# Schematic_v1_0.net
KiCad netlist of a schematic drawn in EAGLE
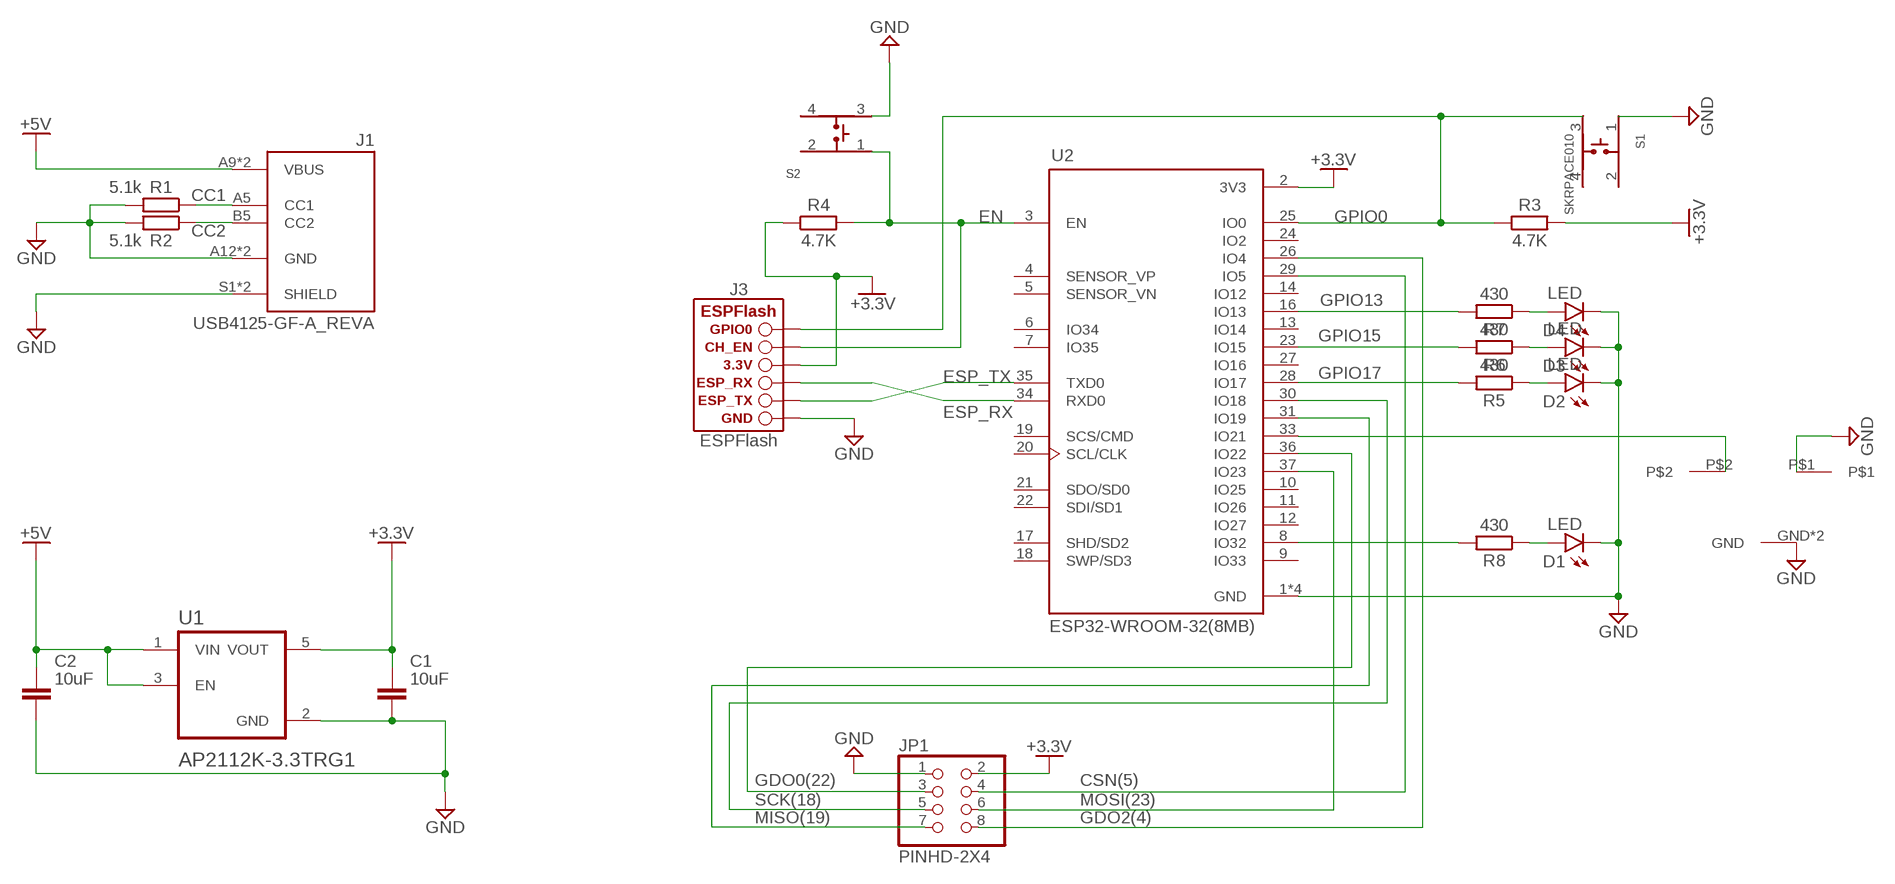
[diagram p0: schematic, sheet 1]

(export (version "E")
  (design (tool "Eeschema 10.0.6"))
  (components
    (comp (ref "C1")
      (value "10uF")
      (footprint "eagle-import:CAPC1608X85")
      (libsource (lib "eagle-import") (part "CCHIP-0603(1608-METRIC)_"))
    )
    (comp (ref "C2")
      (value "10uF")
      (footprint "eagle-import:CAPC1608X85")
      (libsource (lib "eagle-import") (part "CCHIP-0603(1608-METRIC)_"))
    )
    (comp (ref "D1")
      (value "LED")
      (footprint "eagle-import:LEDC1608X80N_FLAT-R")
      (libsource (lib "eagle-import") (part "CHIP-FLAT-R_0603-0.80MM"))
    )
    (comp (ref "D2")
      (value "LED")
      (footprint "eagle-import:LEDC1608X80N_FLAT-R")
      (libsource (lib "eagle-import") (part "CHIP-FLAT-R_0603-0.80MM"))
    )
    (comp (ref "D3")
      (value "LED")
      (footprint "eagle-import:LEDC1608X80N_FLAT-R")
      (libsource (lib "eagle-import") (part "CHIP-FLAT-R_0603-0.80MM"))
    )
    (comp (ref "D4")
      (value "LED")
      (footprint "eagle-import:LEDC1608X80N_FLAT-R")
      (libsource (lib "eagle-import") (part "CHIP-FLAT-R_0603-0.80MM"))
    )
    (comp (ref "J1")
      (value "USB4125-GF-A_REVA")
      (footprint "eagle-import:CUI_UJC-VP-3-SMT-TR")
      (fields (field (name "MANUFACTURER") "CUI Devices"))
      (libsource (lib "eagle-import") (part "UJC-VP-3-SMT-TR"))
    )
    (comp (ref "J3")
      (value "ESPFLASH-2X3-2.54-PLAIN")
      (footprint "eagle-import:2X3-2.54-PLAIN")
      (libsource (lib "eagle-import") (part "ESPFLASH-2X3-2.54-PLAIN"))
    )
    (comp (ref "JP1")
      (value "PINHD-2X4")
      (footprint "eagle-import:2X04")
      (libsource (lib "eagle-import") (part "PINHD-2X4"))
    )
    (comp (ref "R1")
      (value "5.1k")
      (footprint "eagle-import:RESC1608X60")
      (libsource (lib "eagle-import") (part "RCHIP-0603(1608-METRIC)_"))
    )
    (comp (ref "R2")
      (value "5.1k")
      (footprint "eagle-import:RESC1608X60")
      (libsource (lib "eagle-import") (part "RCHIP-0603(1608-METRIC)_"))
    )
    (comp (ref "R3")
      (value "4.7K")
      (footprint "eagle-import:RESC1608X60")
      (libsource (lib "eagle-import") (part "RCHIP-0603(1608-METRIC)_"))
    )
    (comp (ref "R4")
      (value "4.7K")
      (footprint "eagle-import:RESC1608X60")
      (libsource (lib "eagle-import") (part "RCHIP-0603(1608-METRIC)_"))
    )
    (comp (ref "R5")
      (value "430")
      (footprint "eagle-import:RESC1608X60")
      (libsource (lib "eagle-import") (part "RCHIP-0603(1608-METRIC)_"))
    )
    (comp (ref "R6")
      (value "430")
      (footprint "eagle-import:RESC1608X60")
      (libsource (lib "eagle-import") (part "RCHIP-0603(1608-METRIC)_"))
    )
    (comp (ref "R7")
      (value "430")
      (footprint "eagle-import:RESC1608X60")
      (libsource (lib "eagle-import") (part "RCHIP-0603(1608-METRIC)_"))
    )
    (comp (ref "R8")
      (value "430")
      (footprint "eagle-import:RESC1608X60")
      (libsource (lib "eagle-import") (part "RCHIP-0603(1608-METRIC)_"))
    )
    (comp (ref "S1")
      (value "SKRPACE010")
      (footprint "eagle-import:SW_SKRPACE010")
      (fields (field (name "MANUFACTURER") "ALPS"))
      (libsource (lib "eagle-import") (part "SKRPACE010"))
    )
    (comp (ref "S2")
      (value "SKRPACE010")
      (footprint "eagle-import:SW_SKRPACE010")
      (fields (field (name "MANUFACTURER") "ALPS"))
      (libsource (lib "eagle-import") (part "SKRPACE010"))
    )
    (comp (ref "U$1")
      (value "MOMENTARY-SWITCH")
      (footprint "eagle-import:SWITCH-MOMENTARY")
      (libsource (lib "eagle-import") (part "MOMENTARY-SWITCH"))
    )
    (comp (ref "U1")
      (value "AP2112K-3.3TRG1")
      (footprint "eagle-import:SOT95P285X140-5N")
      (fields (field (name "MANUFACTURER") "Diodes Inc."))
      (libsource (lib "eagle-import") (part "AP2112K-3.3TRG1"))
    )
    (comp (ref "U2")
      (value "ESP32-WROOM-32(8MB)")
      (footprint "eagle-import:MODULE_ESP32-WROOM-32(8MB)")
      (fields (field (name "MANUFACTURER") "Espressif Systems"))
      (libsource (lib "eagle-import") (part "ESP32-WROOM-32(8MB)"))
    )
  )
  (nets
    (net (code "1") (name "+3.3V") (class "Default")
      (node (ref "C1") (pin "1") (pinfunction "1_1") (pintype "passive"))
      (node (ref "J3") (pin "2") (pinfunction "3.3V_2") (pintype "passive"))
      (node (ref "JP1") (pin "2") (pinfunction "2_2") (pintype "passive"))
      (node (ref "R3") (pin "2") (pinfunction "2_2") (pintype "passive"))
      (node (ref "R4") (pin "1") (pinfunction "1_1") (pintype "passive"))
      (node (ref "U1") (pin "5") (pinfunction "VOUT_5") (pintype "power_in"))
      (node (ref "U2") (pin "2") (pinfunction "3V3_2") (pintype "power_in"))
    )
    (net (code "2") (name "+5V") (class "Default")
      (node (ref "C2") (pin "1") (pinfunction "1_1") (pintype "passive"))
      (node (ref "J1") (pin "A9") (pinfunction "VBUS_A9") (pintype "power_in"))
      (node (ref "J1") (pin "B9") (pinfunction "VBUS_B9") (pintype "power_in"))
      (node (ref "U1") (pin "1") (pinfunction "VIN_1") (pintype "power_in"))
      (node (ref "U1") (pin "3") (pinfunction "EN_3") (pintype "input"))
    )
    (net (code "3") (name "/CC1") (class "Default")
      (node (ref "J1") (pin "A5") (pinfunction "CC1_A5") (pintype "passive"))
      (node (ref "R1") (pin "1") (pinfunction "1_1") (pintype "passive"))
    )
    (net (code "4") (name "/CC2") (class "Default")
      (node (ref "J1") (pin "B5") (pinfunction "CC2_B5") (pintype "passive"))
      (node (ref "R2") (pin "1") (pinfunction "1_1") (pintype "passive"))
    )
    (net (code "5") (name "/CSN(5)") (class "Default")
      (node (ref "JP1") (pin "4") (pinfunction "4_4") (pintype "passive"))
      (node (ref "U2") (pin "29") (pinfunction "IO5_29") (pintype "bidirectional"))
    )
    (net (code "6") (name "/EN") (class "Default")
      (node (ref "J3") (pin "1") (pinfunction "CH_EN_1") (pintype "passive"))
      (node (ref "R4") (pin "2") (pinfunction "2_2") (pintype "passive"))
      (node (ref "S2") (pin "1") (pinfunction "1_1") (pintype "bidirectional"))
      (node (ref "U2") (pin "3") (pinfunction "EN_3") (pintype "input"))
    )
    (net (code "7") (name "/ESP_RX") (class "Default")
      (node (ref "J3") (pin "5") (pinfunction "ESP_RX_5") (pintype "passive"))
      (node (ref "U2") (pin "34") (pinfunction "RXD0_34") (pintype "bidirectional"))
    )
    (net (code "8") (name "/ESP_TX") (class "Default")
      (node (ref "J3") (pin "3") (pinfunction "ESP_TX_3") (pintype "passive"))
      (node (ref "U2") (pin "35") (pinfunction "TXD0_35") (pintype "bidirectional"))
    )
    (net (code "9") (name "/GDO0(22)") (class "Default")
      (node (ref "JP1") (pin "3") (pinfunction "3_3") (pintype "passive"))
      (node (ref "U2") (pin "36") (pinfunction "IO22_36") (pintype "bidirectional"))
    )
    (net (code "10") (name "/GDO2(4)") (class "Default")
      (node (ref "JP1") (pin "8") (pinfunction "8_8") (pintype "passive"))
      (node (ref "U2") (pin "26") (pinfunction "IO4_26") (pintype "bidirectional"))
    )
    (net (code "11") (name "/GPIO0") (class "Default")
      (node (ref "J3") (pin "6") (pinfunction "GPIO0_6") (pintype "passive"))
      (node (ref "R3") (pin "1") (pinfunction "1_1") (pintype "passive"))
      (node (ref "S1") (pin "3") (pinfunction "3_3") (pintype "bidirectional"))
      (node (ref "U2") (pin "25") (pinfunction "IO0_25") (pintype "bidirectional"))
    )
    (net (code "12") (name "/GPIO13") (class "Default")
      (node (ref "R7") (pin "2") (pinfunction "2_2") (pintype "passive"))
      (node (ref "U2") (pin "16") (pinfunction "IO13_16") (pintype "bidirectional"))
    )
    (net (code "13") (name "/GPIO15") (class "Default")
      (node (ref "R6") (pin "2") (pinfunction "2_2") (pintype "passive"))
      (node (ref "U2") (pin "23") (pinfunction "IO15_23") (pintype "bidirectional"))
    )
    (net (code "14") (name "/GPIO17") (class "Default")
      (node (ref "R5") (pin "2") (pinfunction "2_2") (pintype "passive"))
      (node (ref "U2") (pin "28") (pinfunction "IO17_28") (pintype "bidirectional"))
    )
    (net (code "15") (name "/MISO(19)") (class "Default")
      (node (ref "JP1") (pin "7") (pinfunction "7_7") (pintype "passive"))
      (node (ref "U2") (pin "31") (pinfunction "IO19_31") (pintype "bidirectional"))
    )
    (net (code "16") (name "/MOSI(23)") (class "Default")
      (node (ref "JP1") (pin "6") (pinfunction "6_6") (pintype "passive"))
      (node (ref "U2") (pin "37") (pinfunction "IO23_37") (pintype "bidirectional"))
    )
    (net (code "17") (name "/SCK(18)") (class "Default")
      (node (ref "JP1") (pin "5") (pinfunction "5_5") (pintype "passive"))
      (node (ref "U2") (pin "30") (pinfunction "IO18_30") (pintype "bidirectional"))
    )
    (net (code "18") (name "GND") (class "Default")
      (node (ref "C1") (pin "2") (pinfunction "2_2") (pintype "passive"))
      (node (ref "C2") (pin "2") (pinfunction "2_2") (pintype "passive"))
      (node (ref "D1") (pin "C") (pinfunction "C_C") (pintype "passive"))
      (node (ref "D2") (pin "C") (pinfunction "C_C") (pintype "passive"))
      (node (ref "D3") (pin "C") (pinfunction "C_C") (pintype "passive"))
      (node (ref "D4") (pin "C") (pinfunction "C_C") (pintype "passive"))
      (node (ref "J1") (pin "A12") (pinfunction "GND_A12") (pintype "power_in"))
      (node (ref "J1") (pin "B12") (pinfunction "GND_B12") (pintype "power_in"))
      (node (ref "J1") (pin "S1") (pinfunction "SHIELD_S1") (pintype "passive"))
      (node (ref "J1") (pin "S2") (pinfunction "SHIELD_S2") (pintype "passive"))
      (node (ref "J3") (pin "4") (pinfunction "GND_4") (pintype "passive"))
      (node (ref "JP1") (pin "1") (pinfunction "1_1") (pintype "passive"))
      (node (ref "R1") (pin "2") (pinfunction "2_2") (pintype "passive"))
      (node (ref "R2") (pin "2") (pinfunction "2_2") (pintype "passive"))
      (node (ref "S1") (pin "1") (pinfunction "1_1") (pintype "bidirectional"))
      (node (ref "S2") (pin "3") (pinfunction "3_3") (pintype "bidirectional"))
      (node (ref "U$1") (pin "GND") (pinfunction "GND_GND") (pintype "bidirectional"))
      (node (ref "U$1") (pin "GND_2") (pinfunction "GND_GND_2") (pintype "bidirectional"))
      (node (ref "U$1") (pin "P$1") (pinfunction "P$1_P$1") (pintype "bidirectional"))
      (node (ref "U1") (pin "2") (pinfunction "GND_2") (pintype "power_in"))
      (node (ref "U2") (pin "1") (pinfunction "GND_1") (pintype "power_in"))
      (node (ref "U2") (pin "15") (pinfunction "GND_15") (pintype "power_in"))
      (node (ref "U2") (pin "38") (pinfunction "GND_38") (pintype "power_in"))
      (node (ref "U2") (pin "39") (pinfunction "GND_39") (pintype "power_in"))
    )
    (net (code "19") (name "Net-(D1-PadA)") (class "Default")
      (node (ref "D1") (pin "A") (pinfunction "A_A") (pintype "passive"))
      (node (ref "R8") (pin "1") (pinfunction "1_1") (pintype "passive"))
    )
    (net (code "20") (name "Net-(D2-PadA)") (class "Default")
      (node (ref "D2") (pin "A") (pinfunction "A_A") (pintype "passive"))
      (node (ref "R5") (pin "1") (pinfunction "1_1") (pintype "passive"))
    )
    (net (code "21") (name "Net-(D3-PadA)") (class "Default")
      (node (ref "D3") (pin "A") (pinfunction "A_A") (pintype "passive"))
      (node (ref "R6") (pin "1") (pinfunction "1_1") (pintype "passive"))
    )
    (net (code "22") (name "Net-(D4-PadA)") (class "Default")
      (node (ref "D4") (pin "A") (pinfunction "A_A") (pintype "passive"))
      (node (ref "R7") (pin "1") (pinfunction "1_1") (pintype "passive"))
    )
    (net (code "23") (name "Net-(U2-IO21)") (class "Default")
      (node (ref "U$1") (pin "P$2") (pinfunction "P$2_P$2") (pintype "bidirectional"))
      (node (ref "U2") (pin "33") (pinfunction "IO21_33") (pintype "bidirectional"))
    )
    (net (code "24") (name "Net-(U2-IO32)") (class "Default")
      (node (ref "R8") (pin "2") (pinfunction "2_2") (pintype "passive"))
      (node (ref "U2") (pin "8") (pinfunction "IO32_8") (pintype "bidirectional"))
    )
    (net (code "25") (name "unconnected-(S1-Pad2)") (class "Default")
      (node (ref "S1") (pin "2") (pinfunction "2_2") (pintype "bidirectional"))
    )
    (net (code "26") (name "unconnected-(S1-Pad4)") (class "Default")
      (node (ref "S1") (pin "4") (pinfunction "4_4") (pintype "bidirectional"))
    )
    (net (code "27") (name "unconnected-(S2-Pad2)") (class "Default")
      (node (ref "S2") (pin "2") (pinfunction "2_2") (pintype "bidirectional"))
    )
    (net (code "28") (name "unconnected-(S2-Pad4)") (class "Default")
      (node (ref "S2") (pin "4") (pinfunction "4_4") (pintype "bidirectional"))
    )
    (net (code "29") (name "unconnected-(U2-IO2-Pad24)") (class "Default")
      (node (ref "U2") (pin "24") (pinfunction "IO2_24") (pintype "bidirectional"))
    )
    (net (code "30") (name "unconnected-(U2-IO12-Pad14)") (class "Default")
      (node (ref "U2") (pin "14") (pinfunction "IO12_14") (pintype "bidirectional"))
    )
    (net (code "31") (name "unconnected-(U2-IO14-Pad13)") (class "Default")
      (node (ref "U2") (pin "13") (pinfunction "IO14_13") (pintype "bidirectional"))
    )
    (net (code "32") (name "unconnected-(U2-IO16-Pad27)") (class "Default")
      (node (ref "U2") (pin "27") (pinfunction "IO16_27") (pintype "bidirectional"))
    )
    (net (code "33") (name "unconnected-(U2-IO25-Pad10)") (class "Default")
      (node (ref "U2") (pin "10") (pinfunction "IO25_10") (pintype "bidirectional"))
    )
    (net (code "34") (name "unconnected-(U2-IO26-Pad11)") (class "Default")
      (node (ref "U2") (pin "11") (pinfunction "IO26_11") (pintype "bidirectional"))
    )
    (net (code "35") (name "unconnected-(U2-IO27-Pad12)") (class "Default")
      (node (ref "U2") (pin "12") (pinfunction "IO27_12") (pintype "bidirectional"))
    )
    (net (code "36") (name "unconnected-(U2-IO33-Pad9)") (class "Default")
      (node (ref "U2") (pin "9") (pinfunction "IO33_9") (pintype "bidirectional"))
    )
    (net (code "37") (name "unconnected-(U2-IO34-Pad6)") (class "Default")
      (node (ref "U2") (pin "6") (pinfunction "IO34_6") (pintype "input"))
    )
    (net (code "38") (name "unconnected-(U2-IO35-Pad7)") (class "Default")
      (node (ref "U2") (pin "7") (pinfunction "IO35_7") (pintype "input"))
    )
    (net (code "39") (name "unconnected-(U2-SCL{slash}CLK-Pad20)") (class "Default")
      (node (ref "U2") (pin "20") (pinfunction "SCL/CLK_20") (pintype "bidirectional"))
    )
    (net (code "40") (name "unconnected-(U2-SCS{slash}CMD-Pad19)") (class "Default")
      (node (ref "U2") (pin "19") (pinfunction "SCS/CMD_19") (pintype "bidirectional"))
    )
    (net (code "41") (name "unconnected-(U2-SDI{slash}SD1-Pad22)") (class "Default")
      (node (ref "U2") (pin "22") (pinfunction "SDI/SD1_22") (pintype "bidirectional"))
    )
    (net (code "42") (name "unconnected-(U2-SDO{slash}SD0-Pad21)") (class "Default")
      (node (ref "U2") (pin "21") (pinfunction "SDO/SD0_21") (pintype "bidirectional"))
    )
    (net (code "43") (name "unconnected-(U2-SENSOR_VN-Pad5)") (class "Default")
      (node (ref "U2") (pin "5") (pinfunction "SENSOR_VN_5") (pintype "input"))
    )
    (net (code "44") (name "unconnected-(U2-SENSOR_VP-Pad4)") (class "Default")
      (node (ref "U2") (pin "4") (pinfunction "SENSOR_VP_4") (pintype "input"))
    )
    (net (code "45") (name "unconnected-(U2-SHD{slash}SD2-Pad17)") (class "Default")
      (node (ref "U2") (pin "17") (pinfunction "SHD/SD2_17") (pintype "bidirectional"))
    )
    (net (code "46") (name "unconnected-(U2-SWP{slash}SD3-Pad18)") (class "Default")
      (node (ref "U2") (pin "18") (pinfunction "SWP/SD3_18") (pintype "bidirectional"))
    )
  )
)
